# auxDaqUnitTopDigital2022.net
KiCad netlist of a schematic drawn in EAGLE
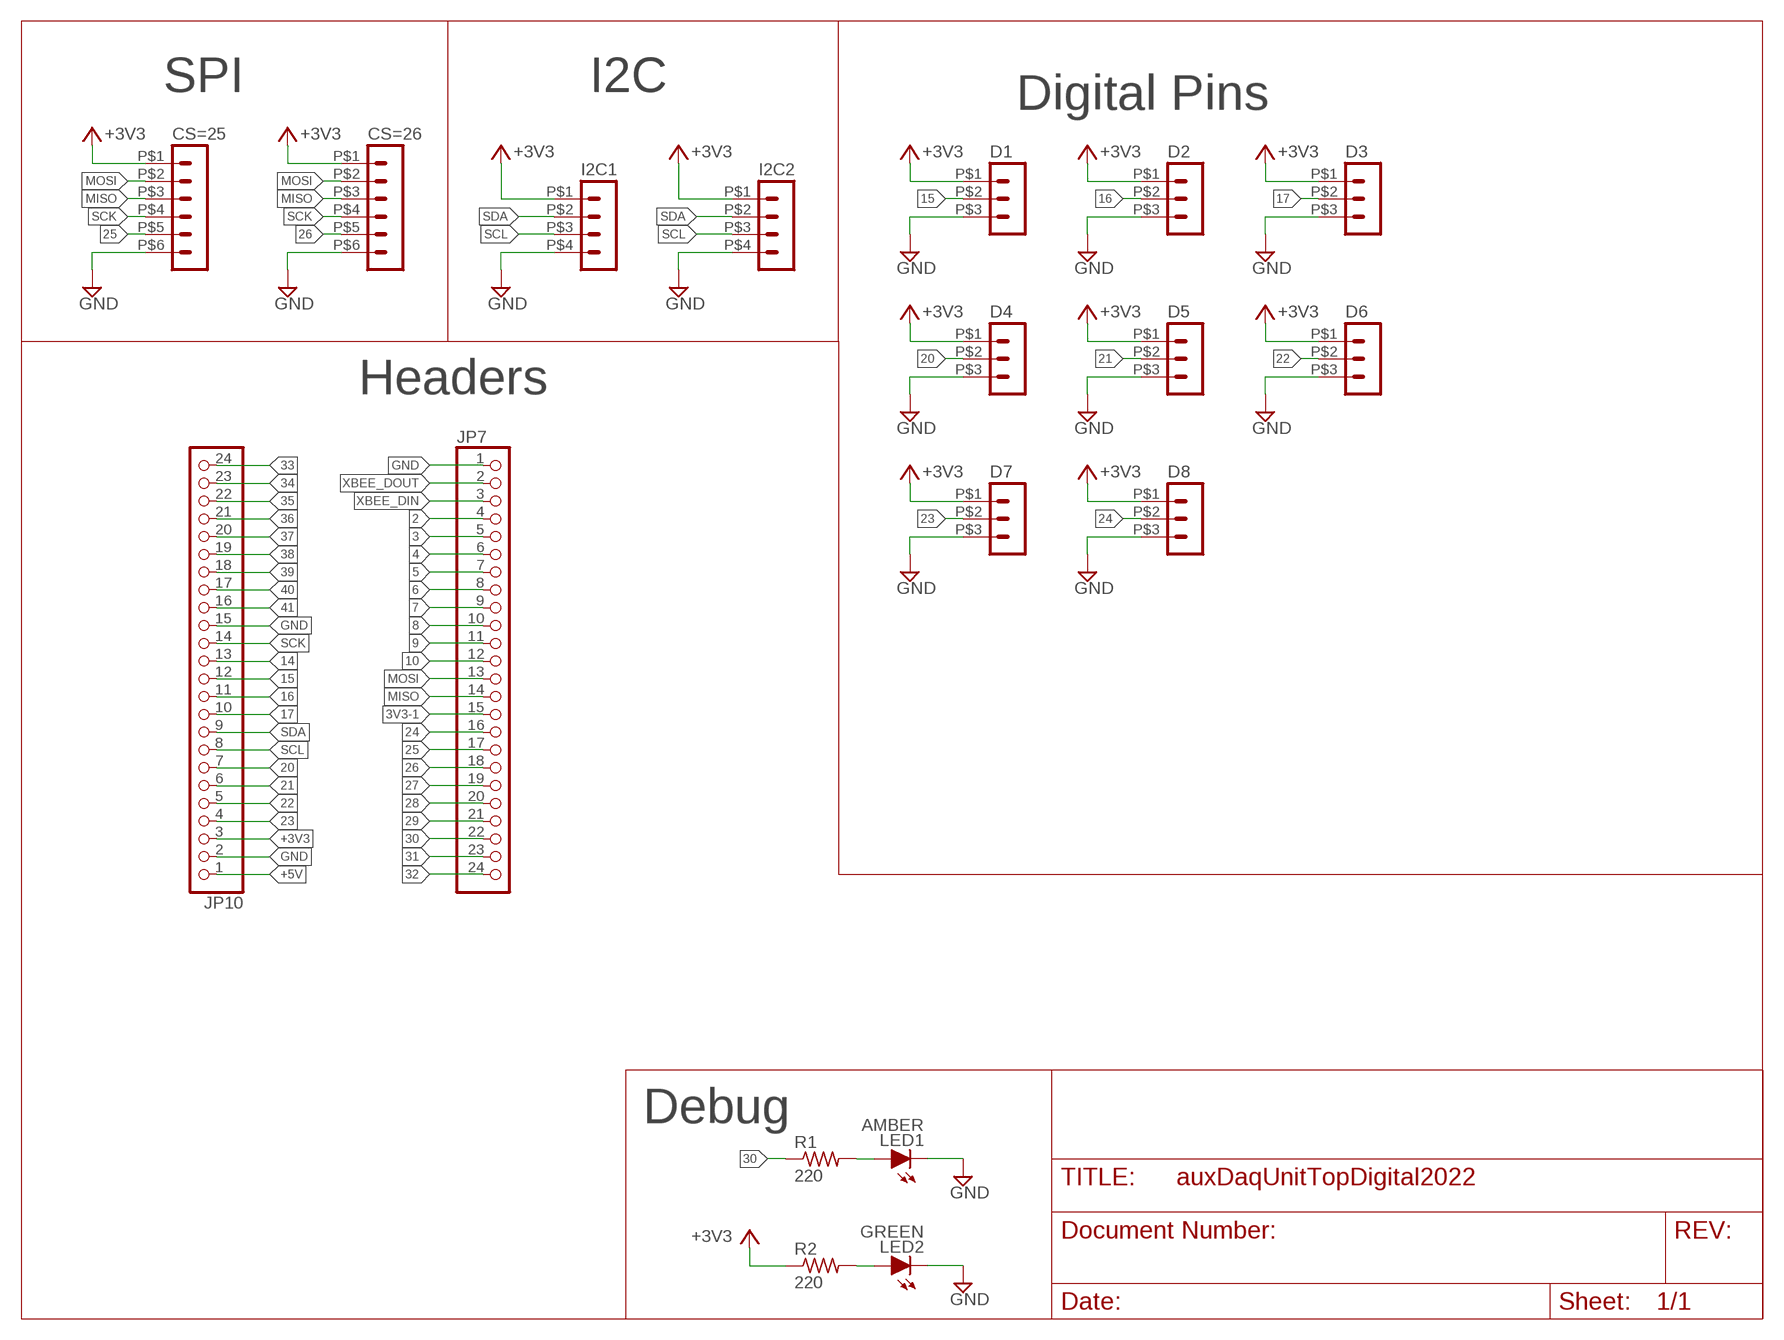
[diagram p0: schematic, sheet 1]

(export (version "E")
  (design (tool "Eeschema 10.0.6"))
  (components
    (comp (ref "CS=25")
      (value "HEADER_POS6_43045-0600")
      (footprint "eagle-import:43045-0600")
      (libsource (lib "eagle-import") (part "HEADER_POS6_?43045-0600"))
    )
    (comp (ref "CS=26")
      (value "HEADER_POS6_43045-0600")
      (footprint "eagle-import:43045-0600")
      (libsource (lib "eagle-import") (part "HEADER_POS6_?43045-0600"))
    )
    (comp (ref "D1")
      (value "HEADER_POS3_43650-0300")
      (footprint "eagle-import:43650-0300")
      (libsource (lib "eagle-import") (part "HEADER_POS3_?43650-0300"))
    )
    (comp (ref "D2")
      (value "HEADER_POS3_43650-0300")
      (footprint "eagle-import:43650-0300")
      (libsource (lib "eagle-import") (part "HEADER_POS3_?43650-0300"))
    )
    (comp (ref "D3")
      (value "HEADER_POS3_43650-0300")
      (footprint "eagle-import:43650-0300")
      (libsource (lib "eagle-import") (part "HEADER_POS3_?43650-0300"))
    )
    (comp (ref "D4")
      (value "HEADER_POS3_43650-0300")
      (footprint "eagle-import:43650-0300")
      (libsource (lib "eagle-import") (part "HEADER_POS3_?43650-0300"))
    )
    (comp (ref "D5")
      (value "HEADER_POS3_43650-0300")
      (footprint "eagle-import:43650-0300")
      (libsource (lib "eagle-import") (part "HEADER_POS3_?43650-0300"))
    )
    (comp (ref "D6")
      (value "HEADER_POS3_43650-0300")
      (footprint "eagle-import:43650-0300")
      (libsource (lib "eagle-import") (part "HEADER_POS3_?43650-0300"))
    )
    (comp (ref "D7")
      (value "HEADER_POS3_43650-0300")
      (footprint "eagle-import:43650-0300")
      (libsource (lib "eagle-import") (part "HEADER_POS3_?43650-0300"))
    )
    (comp (ref "D8")
      (value "HEADER_POS3_43650-0300")
      (footprint "eagle-import:43650-0300")
      (libsource (lib "eagle-import") (part "HEADER_POS3_?43650-0300"))
    )
    (comp (ref "I2C1")
      (value "HEADER_POS4_43045-0401")
      (footprint "eagle-import:43045-0400")
      (libsource (lib "eagle-import") (part "HEADER_POS4_?43045-0401"))
    )
    (comp (ref "I2C2")
      (value "HEADER_POS4_43045-0401")
      (footprint "eagle-import:43045-0400")
      (libsource (lib "eagle-import") (part "HEADER_POS4_?43045-0401"))
    )
    (comp (ref "JP7")
      (value "PINHD-1X24")
      (footprint "eagle-import:1X24")
      (libsource (lib "eagle-import") (part "PINHD-1X24"))
    )
    (comp (ref "JP10")
      (value "PINHD-1X24")
      (footprint "eagle-import:1X24")
      (libsource (lib "eagle-import") (part "PINHD-1X24"))
    )
    (comp (ref "LED1")
      (value "AMBER")
      (footprint "eagle-import:LED-603")
      (libsource (lib "eagle-import") (part "LED-0603"))
    )
    (comp (ref "LED2")
      (value "GREEN")
      (footprint "eagle-import:LED-603")
      (libsource (lib "eagle-import") (part "LED-0603"))
    )
    (comp (ref "R1")
      (value "220")
      (footprint "eagle-import:R0603")
      (libsource (lib "eagle-import") (part "RES_SMDR0603"))
    )
    (comp (ref "R2")
      (value "220")
      (footprint "eagle-import:R0603")
      (libsource (lib "eagle-import") (part "RES_SMDR0603"))
    )
  )
  (nets
    (net (code "1") (name "+3V3") (class "Default")
      (node (ref "CS=25") (pin "P$1") (pinfunction "1_P$1") (pintype "passive"))
      (node (ref "CS=26") (pin "P$1") (pinfunction "1_P$1") (pintype "passive"))
      (node (ref "D1") (pin "P$1") (pinfunction "1_P$1") (pintype "passive"))
      (node (ref "D2") (pin "P$1") (pinfunction "1_P$1") (pintype "passive"))
      (node (ref "D3") (pin "P$1") (pinfunction "1_P$1") (pintype "passive"))
      (node (ref "D4") (pin "P$1") (pinfunction "1_P$1") (pintype "passive"))
      (node (ref "D5") (pin "P$1") (pinfunction "1_P$1") (pintype "passive"))
      (node (ref "D6") (pin "P$1") (pinfunction "1_P$1") (pintype "passive"))
      (node (ref "D7") (pin "P$1") (pinfunction "1_P$1") (pintype "passive"))
      (node (ref "D8") (pin "P$1") (pinfunction "1_P$1") (pintype "passive"))
      (node (ref "I2C1") (pin "P$1") (pinfunction "1_P$1") (pintype "passive"))
      (node (ref "I2C2") (pin "P$1") (pinfunction "1_P$1") (pintype "passive"))
      (node (ref "JP10") (pin "3") (pinfunction "3_3") (pintype "passive"))
      (node (ref "R2") (pin "1") (pinfunction "1_1") (pintype "passive"))
    )
    (net (code "2") (name "+5V") (class "Default")
      (node (ref "JP10") (pin "1") (pinfunction "1_1") (pintype "passive"))
    )
    (net (code "3") (name "2") (class "Default")
      (node (ref "JP7") (pin "4") (pinfunction "4_4") (pintype "passive"))
    )
    (net (code "4") (name "3") (class "Default")
      (node (ref "JP7") (pin "5") (pinfunction "5_5") (pintype "passive"))
    )
    (net (code "5") (name "3V3-1") (class "Default")
      (node (ref "JP7") (pin "15") (pinfunction "15_15") (pintype "passive"))
    )
    (net (code "6") (name "4") (class "Default")
      (node (ref "JP7") (pin "6") (pinfunction "6_6") (pintype "passive"))
    )
    (net (code "7") (name "5") (class "Default")
      (node (ref "JP7") (pin "7") (pinfunction "7_7") (pintype "passive"))
    )
    (net (code "8") (name "6") (class "Default")
      (node (ref "JP7") (pin "8") (pinfunction "8_8") (pintype "passive"))
    )
    (net (code "9") (name "7") (class "Default")
      (node (ref "JP7") (pin "9") (pinfunction "9_9") (pintype "passive"))
    )
    (net (code "10") (name "8") (class "Default")
      (node (ref "JP7") (pin "10") (pinfunction "10_10") (pintype "passive"))
    )
    (net (code "11") (name "9") (class "Default")
      (node (ref "JP7") (pin "11") (pinfunction "11_11") (pintype "passive"))
    )
    (net (code "12") (name "10") (class "Default")
      (node (ref "JP7") (pin "12") (pinfunction "12_12") (pintype "passive"))
    )
    (net (code "13") (name "14") (class "Default")
      (node (ref "JP10") (pin "13") (pinfunction "13_13") (pintype "passive"))
    )
    (net (code "14") (name "15") (class "Default")
      (node (ref "D1") (pin "P$2") (pinfunction "2_P$2") (pintype "passive"))
      (node (ref "JP10") (pin "12") (pinfunction "12_12") (pintype "passive"))
    )
    (net (code "15") (name "16") (class "Default")
      (node (ref "D2") (pin "P$2") (pinfunction "2_P$2") (pintype "passive"))
      (node (ref "JP10") (pin "11") (pinfunction "11_11") (pintype "passive"))
    )
    (net (code "16") (name "17") (class "Default")
      (node (ref "D3") (pin "P$2") (pinfunction "2_P$2") (pintype "passive"))
      (node (ref "JP10") (pin "10") (pinfunction "10_10") (pintype "passive"))
    )
    (net (code "17") (name "20") (class "Default")
      (node (ref "D4") (pin "P$2") (pinfunction "2_P$2") (pintype "passive"))
      (node (ref "JP10") (pin "7") (pinfunction "7_7") (pintype "passive"))
    )
    (net (code "18") (name "21") (class "Default")
      (node (ref "D5") (pin "P$2") (pinfunction "2_P$2") (pintype "passive"))
      (node (ref "JP10") (pin "6") (pinfunction "6_6") (pintype "passive"))
    )
    (net (code "19") (name "22") (class "Default")
      (node (ref "D6") (pin "P$2") (pinfunction "2_P$2") (pintype "passive"))
      (node (ref "JP10") (pin "5") (pinfunction "5_5") (pintype "passive"))
    )
    (net (code "20") (name "23") (class "Default")
      (node (ref "D7") (pin "P$2") (pinfunction "2_P$2") (pintype "passive"))
      (node (ref "JP10") (pin "4") (pinfunction "4_4") (pintype "passive"))
    )
    (net (code "21") (name "24") (class "Default")
      (node (ref "D8") (pin "P$2") (pinfunction "2_P$2") (pintype "passive"))
      (node (ref "JP7") (pin "16") (pinfunction "16_16") (pintype "passive"))
    )
    (net (code "22") (name "25") (class "Default")
      (node (ref "CS=25") (pin "P$5") (pinfunction "5_P$5") (pintype "passive"))
      (node (ref "JP7") (pin "17") (pinfunction "17_17") (pintype "passive"))
    )
    (net (code "23") (name "26") (class "Default")
      (node (ref "CS=26") (pin "P$5") (pinfunction "5_P$5") (pintype "passive"))
      (node (ref "JP7") (pin "18") (pinfunction "18_18") (pintype "passive"))
    )
    (net (code "24") (name "27") (class "Default")
      (node (ref "JP7") (pin "19") (pinfunction "19_19") (pintype "passive"))
    )
    (net (code "25") (name "28") (class "Default")
      (node (ref "JP7") (pin "20") (pinfunction "20_20") (pintype "passive"))
    )
    (net (code "26") (name "29") (class "Default")
      (node (ref "JP7") (pin "21") (pinfunction "21_21") (pintype "passive"))
    )
    (net (code "27") (name "30") (class "Default")
      (node (ref "JP7") (pin "22") (pinfunction "22_22") (pintype "passive"))
      (node (ref "R1") (pin "1") (pinfunction "1_1") (pintype "passive"))
    )
    (net (code "28") (name "31") (class "Default")
      (node (ref "JP7") (pin "23") (pinfunction "23_23") (pintype "passive"))
    )
    (net (code "29") (name "32") (class "Default")
      (node (ref "JP7") (pin "24") (pinfunction "24_24") (pintype "passive"))
    )
    (net (code "30") (name "33") (class "Default")
      (node (ref "JP10") (pin "24") (pinfunction "24_24") (pintype "passive"))
    )
    (net (code "31") (name "34") (class "Default")
      (node (ref "JP10") (pin "23") (pinfunction "23_23") (pintype "passive"))
    )
    (net (code "32") (name "35") (class "Default")
      (node (ref "JP10") (pin "22") (pinfunction "22_22") (pintype "passive"))
    )
    (net (code "33") (name "36") (class "Default")
      (node (ref "JP10") (pin "21") (pinfunction "21_21") (pintype "passive"))
    )
    (net (code "34") (name "37") (class "Default")
      (node (ref "JP10") (pin "20") (pinfunction "20_20") (pintype "passive"))
    )
    (net (code "35") (name "38") (class "Default")
      (node (ref "JP10") (pin "19") (pinfunction "19_19") (pintype "passive"))
    )
    (net (code "36") (name "39") (class "Default")
      (node (ref "JP10") (pin "18") (pinfunction "18_18") (pintype "passive"))
    )
    (net (code "37") (name "40") (class "Default")
      (node (ref "JP10") (pin "17") (pinfunction "17_17") (pintype "passive"))
    )
    (net (code "38") (name "41") (class "Default")
      (node (ref "JP10") (pin "16") (pinfunction "16_16") (pintype "passive"))
    )
    (net (code "39") (name "GND") (class "Default")
      (node (ref "CS=25") (pin "P$6") (pinfunction "6_P$6") (pintype "passive"))
      (node (ref "CS=26") (pin "P$6") (pinfunction "6_P$6") (pintype "passive"))
      (node (ref "D1") (pin "P$3") (pinfunction "3_P$3") (pintype "passive"))
      (node (ref "D2") (pin "P$3") (pinfunction "3_P$3") (pintype "passive"))
      (node (ref "D3") (pin "P$3") (pinfunction "3_P$3") (pintype "passive"))
      (node (ref "D4") (pin "P$3") (pinfunction "3_P$3") (pintype "passive"))
      (node (ref "D5") (pin "P$3") (pinfunction "3_P$3") (pintype "passive"))
      (node (ref "D6") (pin "P$3") (pinfunction "3_P$3") (pintype "passive"))
      (node (ref "D7") (pin "P$3") (pinfunction "3_P$3") (pintype "passive"))
      (node (ref "D8") (pin "P$3") (pinfunction "3_P$3") (pintype "passive"))
      (node (ref "I2C1") (pin "P$4") (pinfunction "4_P$4") (pintype "passive"))
      (node (ref "I2C2") (pin "P$4") (pinfunction "4_P$4") (pintype "passive"))
      (node (ref "JP10") (pin "15") (pinfunction "15_15") (pintype "passive"))
      (node (ref "JP10") (pin "2") (pinfunction "2_2") (pintype "passive"))
      (node (ref "JP7") (pin "1") (pinfunction "1_1") (pintype "passive"))
      (node (ref "LED1") (pin "C") (pinfunction "C_C") (pintype "passive"))
      (node (ref "LED2") (pin "C") (pinfunction "C_C") (pintype "passive"))
    )
    (net (code "40") (name "MISO") (class "Default")
      (node (ref "CS=25") (pin "P$3") (pinfunction "3_P$3") (pintype "passive"))
      (node (ref "CS=26") (pin "P$3") (pinfunction "3_P$3") (pintype "passive"))
      (node (ref "JP7") (pin "14") (pinfunction "14_14") (pintype "passive"))
    )
    (net (code "41") (name "MOSI") (class "Default")
      (node (ref "CS=25") (pin "P$2") (pinfunction "2_P$2") (pintype "passive"))
      (node (ref "CS=26") (pin "P$2") (pinfunction "2_P$2") (pintype "passive"))
      (node (ref "JP7") (pin "13") (pinfunction "13_13") (pintype "passive"))
    )
    (net (code "42") (name "Net-(LED1-PadA)") (class "Default")
      (node (ref "LED1") (pin "A") (pinfunction "A_A") (pintype "passive"))
      (node (ref "R1") (pin "2") (pinfunction "2_2") (pintype "passive"))
    )
    (net (code "43") (name "Net-(LED2-PadA)") (class "Default")
      (node (ref "LED2") (pin "A") (pinfunction "A_A") (pintype "passive"))
      (node (ref "R2") (pin "2") (pinfunction "2_2") (pintype "passive"))
    )
    (net (code "44") (name "SCK") (class "Default")
      (node (ref "CS=25") (pin "P$4") (pinfunction "4_P$4") (pintype "passive"))
      (node (ref "CS=26") (pin "P$4") (pinfunction "4_P$4") (pintype "passive"))
      (node (ref "JP10") (pin "14") (pinfunction "14_14") (pintype "passive"))
    )
    (net (code "45") (name "SCL") (class "Default")
      (node (ref "I2C1") (pin "P$3") (pinfunction "3_P$3") (pintype "passive"))
      (node (ref "I2C2") (pin "P$3") (pinfunction "3_P$3") (pintype "passive"))
      (node (ref "JP10") (pin "8") (pinfunction "8_8") (pintype "passive"))
    )
    (net (code "46") (name "SDA") (class "Default")
      (node (ref "I2C1") (pin "P$2") (pinfunction "2_P$2") (pintype "passive"))
      (node (ref "I2C2") (pin "P$2") (pinfunction "2_P$2") (pintype "passive"))
      (node (ref "JP10") (pin "9") (pinfunction "9_9") (pintype "passive"))
    )
    (net (code "47") (name "XBEE_DIN") (class "Default")
      (node (ref "JP7") (pin "3") (pinfunction "3_3") (pintype "passive"))
    )
    (net (code "48") (name "XBEE_DOUT") (class "Default")
      (node (ref "JP7") (pin "2") (pinfunction "2_2") (pintype "passive"))
    )
  )
)
